# Power.net
KiCad netlist of a schematic drawn in Altium Designer
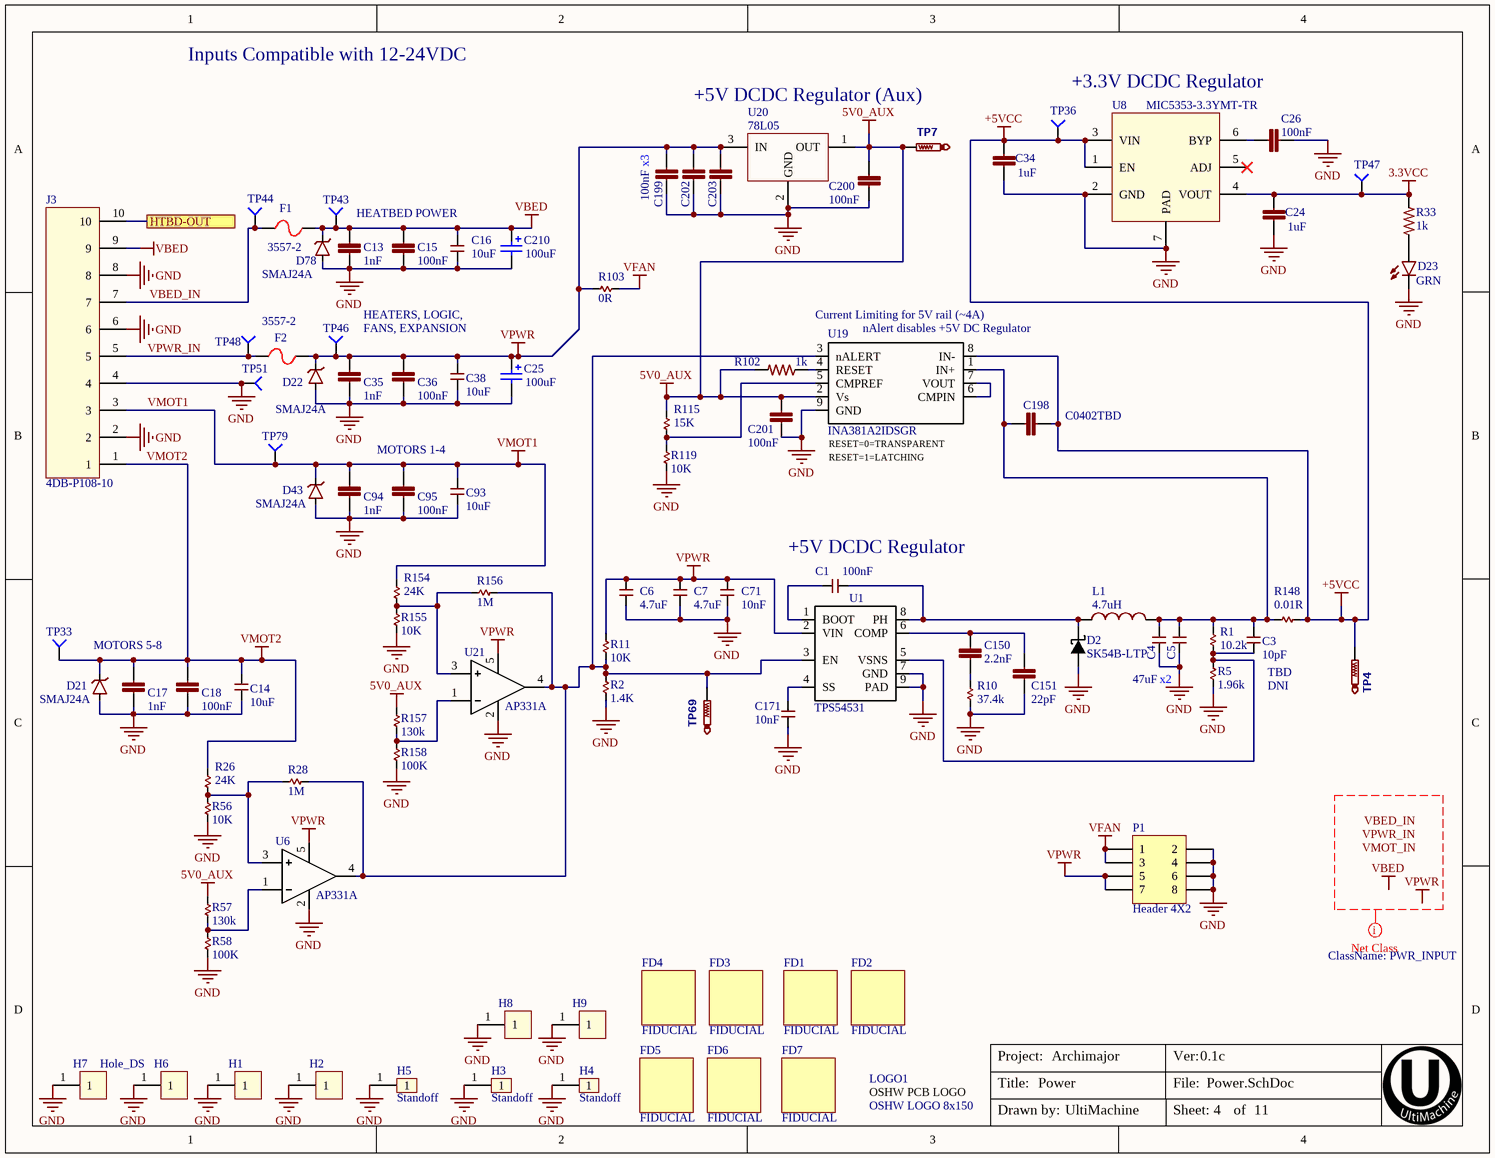
[diagram p0: Power.SchDoc]

(export (version "E")
  (design (tool "Eeschema 10.0.6"))
  (components
    (comp (ref "C1")
      (value "100nF")
      (footprint "C0603")
      (description "CAP CER 0603 100nF 50V 10% X7R")
      (fields (field (name "MANUFACTURER") "Kemet") (field (name "PART") "C0603C104K5RACTU"))
      (libsource (lib "Capacitors") (part "100nF 0603 50V X7R"))
    )
    (comp (ref "C3")
      (value "10pF")
      (footprint "C0402")
      (description "CAP CER 0402 TBD")
      (fields
        (field (name "PART DESCRIPTION") "TBD")
        (field (name "MANUFACTURER") "TBD")
        (field (name "DNI") "DNI")
      )
      (libsource (lib "Capacitors") (part "C0402_TBD"))
    )
    (comp (ref "C4")
      (value "47uF")
      (footprint "C1210")
      (description "CAP CER 47UF 10V X5R 1210")
      (fields (field (name "MANUFACTURER") "Murata") (field (name "PART") "GRM32ER61A476KE20L"))
      (libsource (lib "Capacitors") (part "47uF 1210 10V X5R"))
    )
    (comp (ref "C5")
      (value "47uF")
      (footprint "C1210")
      (description "CAP CER 47UF 10V X5R 1210")
      (fields (field (name "MANUFACTURER") "Murata") (field (name "PART") "GRM32ER61A476KE20L"))
      (libsource (lib "Capacitors") (part "47uF 1210 10V X5R"))
    )
    (comp (ref "C6")
      (value "4.7uF")
      (footprint "C1210")
      (description "CAP CER 4.7UF 50V X7R 1210")
      (fields (field (name "MANUFACTURER") "Murata") (field (name "PART") "GRM32ER71H475KA88L"))
      (libsource (lib "Capacitors") (part "4.7uF 1210 50V X7R"))
    )
    (comp (ref "C7")
      (value "4.7uF")
      (footprint "C1210")
      (description "CAP CER 4.7UF 50V X7R 1210")
      (fields (field (name "MANUFACTURER") "Murata") (field (name "PART") "GRM32ER71H475KA88L"))
      (libsource (lib "Capacitors") (part "4.7uF 1210 50V X7R"))
    )
    (comp (ref "C13")
      (value "1nF")
      (footprint "C0402")
      (description "1000pF 50V Ceramic Capacitor X7R 0402 (1005 Metric) 0.039\" L x 0.020\" W (1.00mm x 0.50mm)")
      (fields (field (name "MANUFACTURER") "Murata") (field (name "PART") "GRM155R71H102KA01D"))
      (libsource (lib "3Delight") (part "CAP 1nF 50V 0402 X7R"))
    )
    (comp (ref "C14")
      (value "10uF")
      (footprint "C1206")
      (description "CAP CER 10UF 50V 10% X5R 1206")
      (fields (field (name "MANUFACTURER") "Murata") (field (name "PART") "490-10756-2-ND"))
      (libsource (lib "Capacitors") (part "10uF 1206 50V X5R"))
    )
    (comp (ref "C15")
      (value "100nF")
      (footprint "C0603")
      (description "CAP CER 0603 100nF 50V 10% X7R")
      (fields (field (name "MANUFACTURER") "Kemet") (field (name "PART") "C0603C104K5RACTU"))
      (libsource (lib "3Delight") (part "C0603C104K5RACTU"))
    )
    (comp (ref "C16")
      (value "10uF")
      (footprint "C1206")
      (description "CAP CER 10UF 50V 10% X5R 1206")
      (fields (field (name "MANUFACTURER") "Murata") (field (name "PART") "490-10756-2-ND"))
      (libsource (lib "Capacitors") (part "10uF 1206 50V X5R"))
    )
    (comp (ref "C17")
      (value "1nF")
      (footprint "C0402")
      (description "1000pF 50V Ceramic Capacitor X7R 0402 (1005 Metric) 0.039\" L x 0.020\" W (1.00mm x 0.50mm)")
      (fields (field (name "MANUFACTURER") "Murata") (field (name "PART") "GRM155R71H102KA01D"))
      (libsource (lib "3Delight") (part "CAP 1nF 50V 0402 X7R"))
    )
    (comp (ref "C18")
      (value "100nF")
      (footprint "C0603")
      (description "CAP CER 0603 100nF 50V 10% X7R")
      (fields (field (name "MANUFACTURER") "Kemet") (field (name "PART") "C0603C104K5RACTU"))
      (libsource (lib "3Delight") (part "C0603C104K5RACTU"))
    )
    (comp (ref "C24")
      (value "1uF")
      (footprint "C0402")
      (description "CAP CER 0402 1uF 6.3V 10% X5R")
      (fields (field (name "MANUFACTURER") "Murata") (field (name "PART") "GRM155R60J105KE19D"))
      (libsource (lib "3Delight") (part "GRM155R60J105KE19D"))
    )
    (comp (ref "C25")
      (value "100uF")
      (footprint "CAP-ELEC-063063077")
      (description "CAP ALUM 100UF 35V 20% SMD")
      (fields (field (name "MANUFACTURER") "Nichicon") (field (name "PART") "UWT1V101MCL1GS"))
      (libsource (lib "3Delight") (part "UWT1V101MCL1GS"))
    )
    (comp (ref "C26")
      (value "100nF")
      (footprint "C0402")
      (description "CAP CER 0402 100nF 16V 10% X7R")
      (fields (field (name "MANUFACTURER") "Murata") (field (name "PART") "GRM155R71C104KA88D"))
      (libsource (lib "") (part "GRM155R71C104KA88D_1"))
    )
    (comp (ref "C34")
      (value "1uF")
      (footprint "C0402")
      (description "CAP CER 0402 1uF 6.3V 10% X5R")
      (fields (field (name "MANUFACTURER") "Murata") (field (name "PART") "GRM155R60J105KE19D"))
      (libsource (lib "3Delight") (part "GRM155R60J105KE19D"))
    )
    (comp (ref "C35")
      (value "1nF")
      (footprint "C0402")
      (description "1000pF 50V Ceramic Capacitor X7R 0402 (1005 Metric) 0.039\" L x 0.020\" W (1.00mm x 0.50mm)")
      (fields (field (name "MANUFACTURER") "Murata") (field (name "PART") "GRM155R71H102KA01D"))
      (libsource (lib "3Delight") (part "CAP 1nF 50V 0402 X7R"))
    )
    (comp (ref "C36")
      (value "100nF")
      (footprint "C0603")
      (description "CAP CER 0603 100nF 50V 10% X7R")
      (fields (field (name "MANUFACTURER") "Kemet") (field (name "PART") "C0603C104K5RACTU"))
      (libsource (lib "3Delight") (part "C0603C104K5RACTU"))
    )
    (comp (ref "C38")
      (value "10uF")
      (footprint "C1206")
      (description "CAP CER 10UF 50V 10% X5R 1206")
      (fields (field (name "MANUFACTURER") "Murata") (field (name "PART") "490-10756-2-ND"))
      (libsource (lib "Capacitors") (part "10uF 1206 50V X5R"))
    )
    (comp (ref "C71")
      (value "10nF")
      (footprint "C0402")
      (description "CAP CER 10nF 50V X7R 0402")
      (fields (field (name "TOLERANCE") "5%") (field (name "MANUFACTURER") "Murata"))
      (libsource (lib "Capacitors") (part "10nF 0402 50V X7R"))
    )
    (comp (ref "C93")
      (value "10uF")
      (footprint "C1206")
      (description "CAP CER 10UF 50V 10% X5R 1206")
      (fields (field (name "MANUFACTURER") "Murata") (field (name "PART") "490-10756-2-ND"))
      (libsource (lib "Capacitors") (part "10uF 1206 50V X5R"))
    )
    (comp (ref "C94")
      (value "1nF")
      (footprint "C0402")
      (description "1000pF 50V Ceramic Capacitor X7R 0402 (1005 Metric) 0.039\" L x 0.020\" W (1.00mm x 0.50mm)")
      (fields (field (name "MANUFACTURER") "Murata") (field (name "PART") "GRM155R71H102KA01D"))
      (libsource (lib "3Delight") (part "CAP 1nF 50V 0402 X7R"))
    )
    (comp (ref "C95")
      (value "100nF")
      (footprint "C0603")
      (description "CAP CER 0603 100nF 50V 10% X7R")
      (fields (field (name "MANUFACTURER") "Kemet") (field (name "PART") "C0603C104K5RACTU"))
      (libsource (lib "3Delight") (part "C0603C104K5RACTU"))
    )
    (comp (ref "C150")
      (value "2.2nF")
      (footprint "C0402")
      (description "CAP CER 0402 2.2nF 25V C0G")
      (fields (field (name "MANUFACTURER") "Kemet") (field (name "PART") "C0402C222J3GACTU"))
      (libsource (lib "Capacitors") (part "2.2nF 25V C0G 0402"))
    )
    (comp (ref "C151")
      (value "22pF")
      (footprint "C0402")
      (description "CAP CER 0402 22pF 50V 5% C0G")
      (fields (field (name "MANUFACTURER") "AVX") (field (name "PART") "04025A220JAT2A"))
      (libsource (lib "Capacitors") (part "22pF 0402 50V C0G"))
    )
    (comp (ref "C171")
      (value "10nF")
      (footprint "C0402")
      (description "CAP CER 10nF 50V X7R 0402")
      (fields (field (name "TOLERANCE") "5%") (field (name "MANUFACTURER") "Murata"))
      (libsource (lib "Capacitors") (part "10nF 0402 50V X7R"))
    )
    (comp (ref "C198")
      (value "C0402TBD")
      (footprint "C0402")
      (description "Capacitor Non Polarized")
      (fields (field (name "PART") "DNI-C0402TBD"))
      (libsource (lib "Capacitors") (part "C0402TBD"))
    )
    (comp (ref "C199")
      (value "100nF")
      (footprint "C0603")
      (description "CAP CER 0603 100nF 50V 10% X7R")
      (fields (field (name "MANUFACTURER") "Kemet") (field (name "PART") "C0603C104K5RACTU"))
      (libsource (lib "3Delight") (part "C0603C104K5RACTU"))
    )
    (comp (ref "C200")
      (value "100nF")
      (footprint "C0402")
      (description "CAP CER 0402 100nF 16V 10% X7R")
      (fields (field (name "MANUFACTURER") "Murata") (field (name "PART") "GRM155R71C104KA88D"))
      (libsource (lib "3Delight") (part "GRM155R71C104KA88D"))
    )
    (comp (ref "C201")
      (value "100nF")
      (footprint "C0402")
      (description "CAP CER 0402 100nF 16V 10% X7R")
      (fields (field (name "MANUFACTURER") "Murata") (field (name "PART") "GRM155R71C104KA88D"))
      (libsource (lib "3Delight") (part "GRM155R71C104KA88D"))
    )
    (comp (ref "C202")
      (value "100nF")
      (footprint "C0603")
      (description "CAP CER 0603 100nF 50V 10% X7R")
      (fields (field (name "MANUFACTURER") "Kemet") (field (name "PART") "C0603C104K5RACTU"))
      (libsource (lib "3Delight") (part "C0603C104K5RACTU"))
    )
    (comp (ref "C203")
      (value "100nF")
      (footprint "C0603")
      (description "CAP CER 0603 100nF 50V 10% X7R")
      (fields (field (name "MANUFACTURER") "Kemet") (field (name "PART") "C0603C104K5RACTU"))
      (libsource (lib "3Delight") (part "C0603C104K5RACTU"))
    )
    (comp (ref "C210")
      (value "100uF")
      (footprint "CAP-ELEC-063063077")
      (description "CAP ALUM 100UF 35V 20% SMD")
      (fields (field (name "MANUFACTURER") "Nichicon") (field (name "PART") "UWT1V101MCL1GS"))
      (libsource (lib "3Delight") (part "UWT1V101MCL1GS"))
    )
    (comp (ref "D2")
      (value "SK54B-LTP")
      (footprint "SMB_DO-214AA_LRG")
      (description "DIODE SCHOTTKY 40V 5A SMB_DO214AA")
      (fields (field (name "MANUFACTURER") "MCC") (field (name "VOLTAGE") "40Vrb"))
      (libsource (lib "Diodes") (part "SK54B"))
    )
    (comp (ref "D21")
      (value "SMAJ24A")
      (footprint "SMA-SM")
      (description "TVS DIODE 24V 38.9V SMA")
      (fields (field (name "MANUFACTURER") "Bourns Inc"))
      (libsource (lib "Diodes") (part "SMAJ24A"))
    )
    (comp (ref "D22")
      (value "SMAJ24A")
      (footprint "SMA-SM")
      (description "TVS DIODE 24V 38.9V SMA")
      (fields (field (name "MANUFACTURER") "Bourns Inc"))
      (libsource (lib "Diodes") (part "SMAJ24A"))
    )
    (comp (ref "D23")
      (value "GRN")
      (footprint "LED2012120")
      (description "LED 0805 Green")
      (fields (field (name "MANUFACTURER") "Dialight") (field (name "PART") "5988170107F"))
      (libsource (lib "LEDs") (part "5988170107F"))
    )
    (comp (ref "D43")
      (value "SMAJ24A")
      (footprint "SMA-SM")
      (description "TVS DIODE 24V 38.9V SMA")
      (fields (field (name "MANUFACTURER") "Bourns Inc"))
      (libsource (lib "Diodes") (part "SMAJ24A"))
    )
    (comp (ref "D78")
      (value "SMAJ24A")
      (footprint "SMA-SM")
      (description "TVS DIODE 24V 38.9V SMA")
      (fields (field (name "MANUFACTURER") "Bourns Inc"))
      (libsource (lib "Diodes") (part "SMAJ24A"))
    )
    (comp (ref "F1")
      (value "3557-2")
      (footprint "3557")
      (description "FUSE PTH ATO")
      (fields (field (name "MANUFACTURER") "Keystone") (field (name "TOLERANCE") "-NA-"))
      (libsource (lib "3Delight") (part "3557-2"))
    )
    (comp (ref "F2")
      (value "3557-2")
      (footprint "3557")
      (description "FUSE PTH ATO")
      (fields (field (name "MANUFACTURER") "Keystone") (field (name "TOLERANCE") "-NA-"))
      (libsource (lib "3Delight") (part "3557-2"))
    )
    (comp (ref "FD1")
      (value "FIDUCIAL")
      (footprint "FIDUCIAL-1X2")
      (fields (field (name "PART") "NOTAPART-Fiducial"))
      (libsource (lib "3Delight") (part "FIDUCIAL"))
    )
    (comp (ref "FD2")
      (value "FIDUCIAL")
      (footprint "FIDUCIAL-1X2")
      (fields (field (name "PART") "NOTAPART-Fiducial"))
      (libsource (lib "3Delight") (part "FIDUCIAL"))
    )
    (comp (ref "FD3")
      (value "FIDUCIAL")
      (footprint "FIDUCIAL-1X2")
      (fields (field (name "PART") "NOTAPART-Fiducial"))
      (libsource (lib "3Delight") (part "FIDUCIAL"))
    )
    (comp (ref "FD4")
      (value "FIDUCIAL")
      (footprint "FIDUCIAL-1X2")
      (fields (field (name "PART") "NOTAPART-Fiducial"))
      (libsource (lib "3Delight") (part "FIDUCIAL"))
    )
    (comp (ref "FD5")
      (value "FIDUCIAL")
      (footprint "FIDUCIAL-1X2")
      (fields (field (name "PART") "NOTAPART-Fiducial"))
      (libsource (lib "3Delight") (part "FIDUCIAL"))
    )
    (comp (ref "FD6")
      (value "FIDUCIAL")
      (footprint "FIDUCIAL-1X2")
      (fields (field (name "PART") "NOTAPART-Fiducial"))
      (libsource (lib "3Delight") (part "FIDUCIAL"))
    )
    (comp (ref "FD7")
      (value "FIDUCIAL")
      (footprint "FIDUCIAL-1X2")
      (fields (field (name "PART") "NOTAPART-Fiducial"))
      (libsource (lib "3Delight") (part "FIDUCIAL"))
    )
    (comp (ref "H1")
      (value "Hole_DS")
      (footprint "Wave_hole_3x7-doubleSided")
      (fields (field (name "PART") "NOTAPART-Hole"))
      (libsource (lib "Archim_0.4") (part "Hole_DS"))
    )
    (comp (ref "H2")
      (value "Hole_DS")
      (footprint "Wave_hole_3x7-doubleSided")
      (fields (field (name "PART") "NOTAPART-Hole"))
      (libsource (lib "Archim_0.4") (part "Hole_DS"))
    )
    (comp (ref "H3")
      (value "Standoff")
      (footprint "Standoff3mmTopConn")
      (description "Mechanical - Top connect")
      (fields (field (name "PART") "NOTAPART-Hole"))
      (libsource (lib "3Delight") (part "Standoff3TopConn"))
    )
    (comp (ref "H4")
      (value "Standoff")
      (footprint "Standoff3mmTopConn")
      (description "Mechanical - Top connect")
      (fields (field (name "PART") "NOTAPART-Hole"))
      (libsource (lib "3Delight") (part "Standoff3TopConn"))
    )
    (comp (ref "H5")
      (value "Standoff")
      (footprint "Standoff3mmTopConn")
      (description "Mechanical - Top connect")
      (fields (field (name "PART") "NOTAPART-Hole"))
      (libsource (lib "3Delight") (part "Standoff3TopConn"))
    )
    (comp (ref "H6")
      (value "Hole_DS")
      (footprint "Wave_hole_3x7-doubleSided")
      (fields (field (name "PART") "NOTAPART-Hole"))
      (libsource (lib "Archim_0.4") (part "Hole_DS"))
    )
    (comp (ref "H7")
      (value "Hole_DS")
      (footprint "Wave_hole_3x7-doubleSided")
      (fields (field (name "PART") "NOTAPART-Hole"))
      (libsource (lib "Archim_0.4") (part "Hole_DS"))
    )
    (comp (ref "H8")
      (value "Hole_DS")
      (footprint "Wave_hole_3x7-doubleSided")
      (fields (field (name "PART") "NOTAPART-Hole"))
      (libsource (lib "Archim_0.4") (part "Hole_DS"))
    )
    (comp (ref "H9")
      (value "Hole_DS")
      (footprint "Wave_hole_3x7-doubleSided")
      (fields (field (name "PART") "NOTAPART-Hole"))
      (libsource (lib "Archim_0.4") (part "Hole_DS"))
    )
    (comp (ref "J3")
      (value "4DB-P108-10")
      (footprint "CON-Barrier-10-8.26mm")
      (description "CONN BARRIER STRIP 10CIRC 0.325\"")
      (fields (field (name "MANUFACTURER") "TE") (field (name "TOLERANCE") "NA"))
      (libsource (lib "Connectors") (part "10 Pos barrier"))
    )
    (comp (ref "L1")
      (value "4.7uH")
      (footprint "IND_10X10")
      (description "FIXED IND 4.7UH 10A 15.5 MOHM")
      (fields (field (name "MANUFACTURER") "Bourns") (field (name "PART") "SRP1038A-4R7M"))
      (libsource (lib "Inductors") (part "4.7uH 10A"))
    )
    (comp (ref "LOGO1")
      (value "OSHW LOGO 8x150")
      (footprint "OSHW_8X150_NOTEXT")
      (fields (field (name "PART") "NOTAPART-OSHW LOGO"))
      (libsource (lib "MISC") (part "OSHW LOGO 8x150"))
    )
    (comp (ref "P1")
      (value "Header 4X2")
      (footprint "HDR2X4")
      (description "Header, 4-Pin, Dual row")
      (fields (field (name "MANUFACTURER") "Multicomp") (field (name "PART") "2213S-08G"))
      (libsource (lib "Miscellaneous Connectors") (part "Header 4X2"))
    )
    (comp (ref "R1")
      (value "10.2k")
      (footprint "R0402")
      (description "RES SMD 10.2K OHM 1% 1/16W 0402")
      (fields (field (name "MANUFACTURER") "Yageo") (field (name "PART") "RC0402FR-0710K2L"))
      (libsource (lib "Resistors") (part "10.2k 1% 0402"))
    )
    (comp (ref "R2")
      (value "1.4K")
      (footprint "R0402")
      (description "RES SMD 1.4K OHM 1% 1/16W 0402")
      (fields (field (name "MANUFACTURER") "Stackpole") (field (name "TOLERANCE") "+/- 1%"))
      (libsource (lib "Resistors") (part "1.4k 1% 0402"))
    )
    (comp (ref "R5")
      (value "1.96k")
      (footprint "R0402")
      (description "RES SMD 1.96K OHM 1% 1/16W 0402")
      (fields (field (name "MANUFACTURER") "Yageo") (field (name "PART") "RC0402FR-071K96L"))
      (libsource (lib "Resistors") (part "1.96k 1% 0402"))
    )
    (comp (ref "R10")
      (value "37.4k")
      (footprint "R0402")
      (description "RES SMD 37.4K OHM 1% 1/16W 0402")
      (fields (field (name "MANUFACTURER") "Yageo") (field (name "PART") "RC0402FR-0737K4L"))
      (libsource (lib "Resistors") (part "37.4K 1% 0402"))
    )
    (comp (ref "R11")
      (value "10K")
      (footprint "R0402")
      (description "RES SMD 10K OHM 1% 1/16W 0402")
      (fields (field (name "MANUFACTURER") "Yageo") (field (name "PART") "RC0402FR-0710KP"))
      (libsource (lib "Resistors") (part "10k 1% 0402"))
    )
    (comp (ref "R26")
      (value "24K")
      (footprint "R0402")
      (description "RES SMD 24K OHM 1% 1/16W 0402")
      (fields (field (name "MANUFACTURER") "Visha Dale") (field (name "TOLERANCE") "+/- 1%"))
      (libsource (lib "Resistors") (part "24k 1% 0402"))
    )
    (comp (ref "R28")
      (value "1M")
      (footprint "Passives:R0402")
      (description "RES 0402 1M 100mW 5%")
      (fields (field (name "MANUFACTURER") "Panasonic") (field (name "PART") "ERJ2GEJ105X"))
      (libsource (lib "Resistors") (part "1M 5% 0402"))
    )
    (comp (ref "R33")
      (value "1k")
      (footprint "R0402")
      (description "RES 0402 1k 63mW 1%")
      (fields (field (name "MANUFACTURER") "Yageo") (field (name "PART") "RC0402FR-071KL"))
      (libsource (lib "3Delight") (part "RK73H1ETTP1001F"))
    )
    (comp (ref "R56")
      (value "10K")
      (footprint "R0402")
      (description "RES SMD 10K OHM 1% 1/16W 0402")
      (fields (field (name "MANUFACTURER") "Yageo") (field (name "PART") "RC0402FR-0710KP"))
      (libsource (lib "Resistors") (part "10k 1% 0402"))
    )
    (comp (ref "R57")
      (value "130k")
      (footprint "Passives:R0402")
      (description "RES SMD 130K OHM 5% 1/16W 0402")
      (fields (field (name "MANUFACTURER") "Yageo") (field (name "PART") "RC0402JR-07130KL"))
      (libsource (lib "Resistors") (part "130k 1% 0402"))
    )
    (comp (ref "R58")
      (value "100K")
      (footprint "Passives:R0402")
      (description "RES SMD 100K OHM 1% 1/16W 0402")
      (fields (field (name "MANUFACTURER") "Samsung") (field (name "PART") "RC1005F104CS"))
      (libsource (lib "Resistors") (part "100k 1% 0402"))
    )
    (comp (ref "R102")
      (value "1k")
      (footprint "R0402")
      (description "RES 0402 1k 63mW 1%")
      (fields (field (name "MANUFACTURER") "Yageo") (field (name "PART") "RC0402FR-071KL"))
      (libsource (lib "3Delight") (part "RK73H1ETTP1001F"))
    )
    (comp (ref "R103")
      (value "0R")
      (footprint "R0603")
      (description "RES SMD 0.0OHM JUMPER 1/10W 0603")
      (fields (field (name "MANUFACTURER") "Bourns") (field (name "PART") "CR0603-J/-000ELF"))
      (libsource (lib "Resistors") (part "0R 0603"))
    )
    (comp (ref "R115")
      (value "15K")
      (footprint "R0402")
      (description "RES SMD 15K 1% 1/16W 0402")
      (fields (field (name "MANUFACTURER") "Samsung") (field (name "PART") "RC1005F153CS"))
      (libsource (lib "Resistors") (part "15K 1% 0402"))
    )
    (comp (ref "R119")
      (value "10K")
      (footprint "R0402")
      (description "RES SMD 10K OHM 1% 1/16W 0402")
      (fields (field (name "MANUFACTURER") "Yageo") (field (name "PART") "RC0402FR-0710KP"))
      (libsource (lib "Resistors") (part "10k 1% 0402"))
    )
    (comp (ref "R148")
      (value "0.01R")
      (footprint "R0805")
      (description "RES 0.01 OHM 1% 1/2W 0805")
      (fields (field (name "MANUFACTURER") "Susumu") (field (name "PART") "KRL1220E-M-R010-F-T5"))
      (libsource (lib "Resistors") (part "0.01R 1% 0805"))
    )
    (comp (ref "R154")
      (value "24K")
      (footprint "R0402")
      (description "RES SMD 24K OHM 1% 1/16W 0402")
      (fields (field (name "MANUFACTURER") "Visha Dale") (field (name "TOLERANCE") "+/- 1%"))
      (libsource (lib "Resistors") (part "24k 1% 0402"))
    )
    (comp (ref "R155")
      (value "10K")
      (footprint "R0402")
      (description "RES SMD 10K OHM 1% 1/16W 0402")
      (fields (field (name "MANUFACTURER") "Yageo") (field (name "PART") "RC0402FR-0710KP"))
      (libsource (lib "Resistors") (part "10k 1% 0402"))
    )
    (comp (ref "R156")
      (value "1M")
      (footprint "Passives:R0402")
      (description "RES 0402 1M 100mW 5%")
      (fields (field (name "MANUFACTURER") "Panasonic") (field (name "PART") "ERJ2GEJ105X"))
      (libsource (lib "Resistors") (part "1M 5% 0402"))
    )
    (comp (ref "R157")
      (value "130k")
      (footprint "Passives:R0402")
      (description "RES SMD 130K OHM 5% 1/16W 0402")
      (fields (field (name "MANUFACTURER") "Yageo") (field (name "PART") "RC0402JR-07130KL"))
      (libsource (lib "Resistors") (part "130k 1% 0402"))
    )
    (comp (ref "R158")
      (value "100K")
      (footprint "Passives:R0402")
      (description "RES SMD 100K OHM 1% 1/16W 0402")
      (fields (field (name "MANUFACTURER") "Samsung") (field (name "PART") "RC1005F104CS"))
      (libsource (lib "Resistors") (part "100k 1% 0402"))
    )
    (comp (ref "TP4")
      (value "TestPoint")
      (footprint "TP1-27")
      (description "Test Point")
      (libsource (lib "") (part "TestPoint_1"))
    )
    (comp (ref "TP7")
      (value "TestPoint")
      (footprint "TP1-27")
      (description "Test Point")
      (libsource (lib "3Delight") (part "TestPoint"))
    )
    (comp (ref "TP33")
      (value "TP4")
      (footprint "TP-2")
      (description "Socket")
      (fields (field (name "PART") "NOTAPART-Testpoint"))
      (libsource (lib "Archim") (part "Socket"))
    )
    (comp (ref "TP36")
      (value "TP4")
      (footprint "TP-2")
      (description "Socket")
      (fields (field (name "PART") "NOTAPART-Testpoint"))
      (libsource (lib "Archim") (part "Socket"))
    )
    (comp (ref "TP43")
      (value "TP4")
      (footprint "TP-2")
      (description "Socket")
      (fields (field (name "PART") "NOTAPART-Testpoint"))
      (libsource (lib "Archim") (part "Socket"))
    )
    (comp (ref "TP44")
      (value "TP4")
      (footprint "TP-2")
      (description "Socket")
      (fields (field (name "PART") "NOTAPART-Testpoint"))
      (libsource (lib "Archim") (part "Socket"))
    )
    (comp (ref "TP46")
      (value "TP4")
      (footprint "TP-2")
      (description "Socket")
      (fields (field (name "PART") "NOTAPART-Testpoint"))
      (libsource (lib "Archim") (part "Socket"))
    )
    (comp (ref "TP47")
      (value "TP4")
      (footprint "TP-2")
      (description "Socket")
      (fields (field (name "PART") "NOTAPART-Testpoint"))
      (libsource (lib "Archim") (part "Socket"))
    )
    (comp (ref "TP48")
      (value "TP4")
      (footprint "TP-2")
      (description "Socket")
      (fields (field (name "PART") "NOTAPART-Testpoint"))
      (libsource (lib "Archim") (part "Socket"))
    )
    (comp (ref "TP51")
      (value "TP4")
      (footprint "TP-2")
      (description "Socket")
      (fields (field (name "PART") "NOTAPART-Testpoint"))
      (libsource (lib "Archim") (part "Socket"))
    )
    (comp (ref "TP69")
      (value "TestPoint")
      (footprint "TP1-27")
      (description "Test Point")
      (libsource (lib "") (part "TestPoint_1"))
    )
    (comp (ref "TP79")
      (value "TP4")
      (footprint "TP-2")
      (description "Socket")
      (fields (field (name "PART") "NOTAPART-Testpoint"))
      (libsource (lib "Archim") (part "Socket"))
    )
    (comp (ref "U1")
      (value "TPS54531")
      (footprint "SOIC127P600X170_HS-9L")
      (description "IC REG BUCK ADJ 5A 8SOPWRPAD")
      (fields (field (name "MANUFACTURER") "TI") (field (name "PART") "TPS54531DDAR"))
      (libsource (lib "ICs-Power") (part "TPS54531"))
    )
    (comp (ref "U6")
      (value "AP331A")
      (footprint "SOT23-5")
      (description "IC QUAD DIFF COMPARATOR 14 -SOIC")
      (fields (field (name "PART") "AP331AWG-7") (field (name "MANUFACTURER") "TEXAS INSTRUMENTS"))
      (libsource (lib "ICs-Analog") (part "AP331A"))
    )
    (comp (ref "U8")
      (value "MIC5353-3.3YMT-TR")
      (footprint "TDFN1616-6LD-PL-1")
      (description "LDO 3.3V 500mA - low ESR Cout")
      (fields (field (name "MANUFACTURER") "Microchip") (field (name "TOLERANCE") "-NA-"))
      (libsource (lib "Tigershark3D") (part "MIC5353-3.3YMT-TR"))
    )
    (comp (ref "U19")
      (value "INA381A2IDSGR")
      (footprint "WSON8_2x2mm")
      (description "IC COMPARATOR BIDIR 8WSON")
      (fields (field (name "MANUFACTURER") "TI") (field (name "TOLERANCE") "-NA-"))
      (libsource (lib "ICs-Analog") (part "INA381_ALT"))
    )
    (comp (ref "U20")
      (value "78L05")
      (footprint "SOT-89-3")
      (description "IC REG LINEAR 5V 100MA SOT89-3")
      (fields (field (name "MANUFACTURER") "ST") (field (name "PART") "L78L05ABUTR"))
      (libsource (lib "ICs-Power") (part "78L05"))
    )
    (comp (ref "U21")
      (value "AP331A")
      (footprint "SOT23-5")
      (description "IC QUAD DIFF COMPARATOR 14 -SOIC")
      (fields (field (name "PART") "AP331AWG-7") (field (name "MANUFACTURER") "TEXAS INSTRUMENTS"))
      (libsource (lib "ICs-Analog") (part "AP331A"))
    )
  )
  (nets
    (net (code "1") (name "+5VCC") (class "Default")
      (node (ref "C198") (pin "1") (pinfunction "1_1") (pintype "passive"))
      (node (ref "C34") (pin "1") (pinfunction "1_1") (pintype "passive"))
      (node (ref "R148") (pin "2") (pinfunction "2_2") (pintype "passive"))
      (node (ref "TP36") (pin "1") (pinfunction "1_1") (pintype "passive"))
      (node (ref "TP4") (pin "TP") (pinfunction "TP_TP") (pintype "passive"))
      (node (ref "U19") (pin "8") (pinfunction "IN-_8") (pintype "power_in"))
      (node (ref "U8") (pin "1") (pinfunction "EN_1") (pintype "power_in"))
      (node (ref "U8") (pin "3") (pinfunction "VIN_3") (pintype "power_in"))
    )
    (net (code "2") (name "/HTBD-OUT") (class "Default")
      (node (ref "J3") (pin "10") (pinfunction "10_10") (pintype "passive"))
    )
    (net (code "3") (name "/VBED_IN") (class "Default")
      (node (ref "F1") (pin "1") (pinfunction "1_1") (pintype "passive"))
      (node (ref "J3") (pin "7") (pinfunction "7_7") (pintype "passive"))
      (node (ref "TP44") (pin "1") (pinfunction "1_1") (pintype "passive"))
    )
    (net (code "5") (name "/VPWR_IN") (class "Default")
      (node (ref "F2") (pin "1") (pinfunction "1_1") (pintype "passive"))
      (node (ref "J3") (pin "5") (pinfunction "5_5") (pintype "passive"))
      (node (ref "TP48") (pin "1") (pinfunction "1_1") (pintype "passive"))
    )
    (net (code "6") (name "3.3VCC") (class "Default")
      (node (ref "C24") (pin "1") (pinfunction "1_1") (pintype "passive"))
      (node (ref "R33") (pin "2") (pinfunction "2_2") (pintype "passive"))
      (node (ref "TP47") (pin "1") (pinfunction "1_1") (pintype "passive"))
      (node (ref "U8") (pin "4") (pinfunction "VOUT_4") (pintype "power_in"))
    )
    (net (code "7") (name "5V0_AUX") (class "Default")
      (node (ref "C200") (pin "2") (pinfunction "2_2") (pintype "passive"))
      (node (ref "C201") (pin "2") (pinfunction "2_2") (pintype "passive"))
      (node (ref "R102") (pin "2") (pinfunction "2_2") (pintype "passive"))
      (node (ref "R115") (pin "2") (pinfunction "2_2") (pintype "passive"))
      (node (ref "R157") (pin "2") (pinfunction "2_2") (pintype "passive"))
      (node (ref "R57") (pin "2") (pinfunction "2_2") (pintype "passive"))
      (node (ref "TP7") (pin "TP") (pinfunction "TP_TP") (pintype "passive"))
      (node (ref "U19") (pin "2") (pinfunction "Vs_2") (pintype "power_in"))
      (node (ref "U20") (pin "1") (pinfunction "OUT_1") (pintype "power_in"))
    )
    (net (code "8") (name "GND") (class "Default")
      (node (ref "C13") (pin "2") (pinfunction "2_2") (pintype "passive"))
      (node (ref "C14") (pin "1") (pinfunction "1_1") (pintype "passive"))
      (node (ref "C15") (pin "2") (pinfunction "2_2") (pintype "passive"))
      (node (ref "C151") (pin "1") (pinfunction "1_1") (pintype "passive"))
      (node (ref "C16") (pin "1") (pinfunction "1_1") (pintype "passive"))
      (node (ref "C17") (pin "2") (pinfunction "2_2") (pintype "passive"))
      (node (ref "C171") (pin "1") (pinfunction "1_1") (pintype "passive"))
      (node (ref "C18") (pin "2") (pinfunction "2_2") (pintype "passive"))
      (node (ref "C199") (pin "2") (pinfunction "2_2") (pintype "passive"))
      (node (ref "C200") (pin "1") (pinfunction "1_1") (pintype "passive"))
      (node (ref "C201") (pin "1") (pinfunction "1_1") (pintype "passive"))
      (node (ref "C202") (pin "2") (pinfunction "2_2") (pintype "passive"))
      (node (ref "C203") (pin "2") (pinfunction "2_2") (pintype "passive"))
      (node (ref "C210") (pin "2") (pinfunction "2_2") (pintype "passive"))
      (node (ref "C24") (pin "2") (pinfunction "2_2") (pintype "passive"))
      (node (ref "C25") (pin "2") (pinfunction "2_2") (pintype "passive"))
      (node (ref "C26") (pin "2") (pinfunction "2_2") (pintype "passive"))
      (node (ref "C34") (pin "2") (pinfunction "2_2") (pintype "passive"))
      (node (ref "C35") (pin "2") (pinfunction "2_2") (pintype "passive"))
      (node (ref "C36") (pin "2") (pinfunction "2_2") (pintype "passive"))
      (node (ref "C38") (pin "1") (pinfunction "1_1") (pintype "passive"))
      (node (ref "C4") (pin "1") (pinfunction "1_1") (pintype "passive"))
      (node (ref "C5") (pin "1") (pinfunction "1_1") (pintype "passive"))
      (node (ref "C6") (pin "1") (pinfunction "1_1") (pintype "passive"))
      (node (ref "C7") (pin "1") (pinfunction "1_1") (pintype "passive"))
      (node (ref "C71") (pin "1") (pinfunction "1_1") (pintype "passive"))
      (node (ref "C93") (pin "1") (pinfunction "1_1") (pintype "passive"))
      (node (ref "C94") (pin "2") (pinfunction "2_2") (pintype "passive"))
      (node (ref "C95") (pin "2") (pinfunction "2_2") (pintype "passive"))
      (node (ref "D2") (pin "A") (pinfunction "ANODE_A") (pintype "passive"))
      (node (ref "D21") (pin "A") (pinfunction "A_A") (pintype "passive"))
      (node (ref "D22") (pin "A") (pinfunction "A_A") (pintype "passive"))
      (node (ref "D23") (pin "C") (pinfunction "C_C") (pintype "passive"))
      (node (ref "D43") (pin "A") (pinfunction "A_A") (pintype "passive"))
      (node (ref "D78") (pin "A") (pinfunction "A_A") (pintype "passive"))
      (node (ref "H1") (pin "1") (pinfunction "1_1") (pintype "power_in"))
      (node (ref "H2") (pin "1") (pinfunction "1_1") (pintype "power_in"))
      (node (ref "H3") (pin "1") (pinfunction "1_1") (pintype "power_in"))
      (node (ref "H4") (pin "1") (pinfunction "1_1") (pintype "power_in"))
      (node (ref "H5") (pin "1") (pinfunction "1_1") (pintype "power_in"))
      (node (ref "H6") (pin "1") (pinfunction "1_1") (pintype "power_in"))
      (node (ref "H7") (pin "1") (pinfunction "1_1") (pintype "power_in"))
      (node (ref "H8") (pin "1") (pinfunction "1_1") (pintype "power_in"))
      (node (ref "H9") (pin "1") (pinfunction "1_1") (pintype "power_in"))
      (node (ref "J3") (pin "2") (pinfunction "2_2") (pintype "passive"))
      (node (ref "J3") (pin "4") (pinfunction "4_4") (pintype "passive"))
      (node (ref "J3") (pin "6") (pinfunction "6_6") (pintype "passive"))
      (node (ref "J3") (pin "8") (pinfunction "8_8") (pintype "passive"))
      (node (ref "P1") (pin "2") (pinfunction "2_2") (pintype "passive"))
      (node (ref "P1") (pin "4") (pinfunction "4_4") (pintype "passive"))
      (node (ref "P1") (pin "6") (pinfunction "6_6") (pintype "passive"))
      (node (ref "P1") (pin "8") (pinfunction "8_8") (pintype "passive"))
      (node (ref "R10") (pin "1") (pinfunction "1_1") (pintype "passive"))
      (node (ref "R119") (pin "1") (pinfunction "1_1") (pintype "passive"))
      (node (ref "R155") (pin "1") (pinfunction "1_1") (pintype "passive"))
      (node (ref "R158") (pin "1") (pinfunction "1_1") (pintype "passive"))
      (node (ref "R2") (pin "1") (pinfunction "1_1") (pintype "passive"))
      (node (ref "R5") (pin "1") (pinfunction "1_1") (pintype "passive"))
      (node (ref "R56") (pin "1") (pinfunction "1_1") (pintype "passive"))
      (node (ref "R58") (pin "1") (pinfunction "1_1") (pintype "passive"))
      (node (ref "TP51") (pin "1") (pinfunction "1_1") (pintype "passive"))
      (node (ref "U1") (pin "7") (pinfunction "GND_7") (pintype "passive"))
      (node (ref "U1") (pin "9") (pinfunction "PAD_9") (pintype "passive"))
      (node (ref "U19") (pin "9") (pinfunction "GND_9") (pintype "power_in"))
      (node (ref "U20") (pin "2") (pinfunction "GND_2") (pintype "power_in"))
      (node (ref "U21") (pin "2") (pinfunction "GND_2") (pintype "power_in"))
      (node (ref "U6") (pin "2") (pinfunction "GND_2") (pintype "power_in"))
      (node (ref "U8") (pin "2") (pinfunction "GND_2") (pintype "power_in"))
      (node (ref "U8") (pin "7") (pinfunction "PAD_7") (pintype "power_in"))
    )
    (net (code "9") (name "Net-(C150-Pad1)") (class "Default")
      (node (ref "C150") (pin "1") (pinfunction "1_1") (pintype "passive"))
      (node (ref "R10") (pin "2") (pinfunction "2_2") (pintype "passive"))
    )
    (net (code "10") (name "Net-(D2-CATHODE)") (class "Default")
      (node (ref "C1") (pin "2") (pinfunction "2_2") (pintype "passive"))
      (node (ref "D2") (pin "K") (pinfunction "CATHODE_K") (pintype "passive"))
      (node (ref "L1") (pin "1") (pinfunction "1_1") (pintype "passive"))
      (node (ref "U1") (pin "8") (pinfunction "PH_8") (pintype "passive"))
    )
    (net (code "11") (name "Net-(D23-PadA)") (class "Default")
      (node (ref "D23") (pin "A") (pinfunction "A_A") (pintype "passive"))
      (node (ref "R33") (pin "1") (pinfunction "1_1") (pintype "passive"))
    )
    (net (code "12") (name "Net-(U1-BOOT)") (class "Default")
      (node (ref "C1") (pin "1") (pinfunction "1_1") (pintype "passive"))
      (node (ref "U1") (pin "1") (pinfunction "BOOT_1") (pintype "passive"))
    )
    (net (code "13") (name "Net-(U1-COMP)") (class "Default")
      (node (ref "C150") (pin "2") (pinfunction "2_2") (pintype "passive"))
      (node (ref "C151") (pin "2") (pinfunction "2_2") (pintype "passive"))
      (node (ref "U1") (pin "6") (pinfunction "COMP_6") (pintype "passive"))
    )
    (net (code "14") (name "Net-(U1-EN)") (class "Default")
      (node (ref "R11") (pin "1") (pinfunction "1_1") (pintype "passive"))
      (node (ref "R156") (pin "1") (pinfunction "1_1") (pintype "passive"))
      (node (ref "R2") (pin "2") (pinfunction "2_2") (pintype "passive"))
      (node (ref "R28") (pin "1") (pinfunction "1_1") (pintype "passive"))
      (node (ref "TP69") (pin "TP") (pinfunction "TP_TP") (pintype "passive"))
      (node (ref "U1") (pin "3") (pinfunction "EN_3") (pintype "passive"))
      (node (ref "U19") (pin "3") (pinfunction "nALERT_3") (pintype "power_in"))
      (node (ref "U21") (pin "4") (pinfunction "OUT_4") (pintype "passive"))
      (node (ref "U6") (pin "4") (pinfunction "OUT_4") (pintype "passive"))
    )
    (net (code "15") (name "Net-(U1-SS)") (class "Default")
      (node (ref "C171") (pin "2") (pinfunction "2_2") (pintype "passive"))
      (node (ref "U1") (pin "4") (pinfunction "SS_4") (pintype "passive"))
    )
    (net (code "16") (name "Net-(U1-VSNS)") (class "Default")
      (node (ref "C3") (pin "1") (pinfunction "1_1") (pintype "passive"))
      (node (ref "R1") (pin "2") (pinfunction "2_2") (pintype "passive"))
      (node (ref "R5") (pin "2") (pinfunction "2_2") (pintype "passive"))
      (node (ref "U1") (pin "5") (pinfunction "VSNS_5") (pintype "passive"))
    )
    (net (code "17") (name "Net-(U6-IN+)") (class "Default")
      (node (ref "R26") (pin "2") (pinfunction "2_2") (pintype "passive"))
      (node (ref "R28") (pin "2") (pinfunction "2_2") (pintype "passive"))
      (node (ref "R56") (pin "2") (pinfunction "2_2") (pintype "passive"))
      (node (ref "U6") (pin "3") (pinfunction "IN+_3") (pintype "passive"))
    )
    (net (code "18") (name "Net-(U6-IN-)") (class "Default")
      (node (ref "R57") (pin "1") (pinfunction "1_1") (pintype "passive"))
      (node (ref "R58") (pin "2") (pinfunction "2_2") (pintype "passive"))
      (node (ref "U6") (pin "1") (pinfunction "IN-_1") (pintype "passive"))
    )
    (net (code "19") (name "Net-(U8-BYP)") (class "Default")
      (node (ref "C26") (pin "1") (pinfunction "1_1") (pintype "passive"))
      (node (ref "U8") (pin "6") (pinfunction "BYP_6") (pintype "power_in"))
    )
    (net (code "20") (name "Net-(U19-CMPIN)") (class "Default")
      (node (ref "U19") (pin "6") (pinfunction "CMPIN_6") (pintype "power_in"))
      (node (ref "U19") (pin "7") (pinfunction "VOUT_7") (pintype "power_in"))
    )
    (net (code "21") (name "Net-(U19-CMPREF)") (class "Default")
      (node (ref "R115") (pin "1") (pinfunction "1_1") (pintype "passive"))
      (node (ref "R119") (pin "2") (pinfunction "2_2") (pintype "passive"))
      (node (ref "U19") (pin "5") (pinfunction "CMPREF_5") (pintype "power_in"))
    )
    (net (code "22") (name "Net-(U19-IN+)") (class "Default")
      (node (ref "C198") (pin "2") (pinfunction "2_2") (pintype "passive"))
      (node (ref "C3") (pin "2") (pinfunction "2_2") (pintype "passive"))
      (node (ref "C4") (pin "2") (pinfunction "2_2") (pintype "passive"))
      (node (ref "C5") (pin "2") (pinfunction "2_2") (pintype "passive"))
      (node (ref "L1") (pin "2") (pinfunction "2_2") (pintype "passive"))
      (node (ref "R1") (pin "1") (pinfunction "1_1") (pintype "passive"))
      (node (ref "R148") (pin "1") (pinfunction "1_1") (pintype "passive"))
      (node (ref "U19") (pin "1") (pinfunction "IN+_1") (pintype "power_in"))
    )
    (net (code "23") (name "Net-(U19-RESET)") (class "Default")
      (node (ref "R102") (pin "1") (pinfunction "1_1") (pintype "passive"))
      (node (ref "U19") (pin "4") (pinfunction "RESET_4") (pintype "power_in"))
    )
    (net (code "24") (name "Net-(U21-IN+)") (class "Default")
      (node (ref "R154") (pin "2") (pinfunction "2_2") (pintype "passive"))
      (node (ref "R155") (pin "2") (pinfunction "2_2") (pintype "passive"))
      (node (ref "R156") (pin "2") (pinfunction "2_2") (pintype "passive"))
      (node (ref "U21") (pin "3") (pinfunction "IN+_3") (pintype "passive"))
    )
    (net (code "25") (name "Net-(U21-IN-)") (class "Default")
      (node (ref "R157") (pin "1") (pinfunction "1_1") (pintype "passive"))
      (node (ref "R158") (pin "2") (pinfunction "2_2") (pintype "passive"))
      (node (ref "U21") (pin "1") (pinfunction "IN-_1") (pintype "passive"))
    )
    (net (code "26") (name "VBED") (class "Default")
      (node (ref "C13") (pin "1") (pinfunction "1_1") (pintype "passive"))
      (node (ref "C15") (pin "1") (pinfunction "1_1") (pintype "passive"))
      (node (ref "C16") (pin "2") (pinfunction "2_2") (pintype "passive"))
      (node (ref "C210") (pin "1") (pinfunction "1_1") (pintype "passive"))
      (node (ref "D78") (pin "K") (pinfunction "K_K") (pintype "passive"))
      (node (ref "F1") (pin "2") (pinfunction "2_2") (pintype "passive"))
      (node (ref "J3") (pin "9") (pinfunction "9_9") (pintype "passive"))
      (node (ref "TP43") (pin "1") (pinfunction "1_1") (pintype "passive"))
    )
    (net (code "27") (name "VFAN") (class "Default")
      (node (ref "P1") (pin "1") (pinfunction "1_1") (pintype "passive"))
      (node (ref "P1") (pin "3") (pinfunction "3_3") (pintype "passive"))
      (node (ref "R103") (pin "2") (pinfunction "2_2") (pintype "passive"))
    )
    (net (code "28") (name "VMOT1") (class "Default")
      (node (ref "C93") (pin "2") (pinfunction "2_2") (pintype "passive"))
      (node (ref "C94") (pin "1") (pinfunction "1_1") (pintype "passive"))
      (node (ref "C95") (pin "1") (pinfunction "1_1") (pintype "passive"))
      (node (ref "D43") (pin "K") (pinfunction "K_K") (pintype "passive"))
      (node (ref "J3") (pin "3") (pinfunction "3_3") (pintype "passive"))
      (node (ref "R154") (pin "1") (pinfunction "1_1") (pintype "passive"))
      (node (ref "TP79") (pin "1") (pinfunction "1_1") (pintype "passive"))
    )
    (net (code "29") (name "VMOT2") (class "Default")
      (node (ref "C14") (pin "2") (pinfunction "2_2") (pintype "passive"))
      (node (ref "C17") (pin "1") (pinfunction "1_1") (pintype "passive"))
      (node (ref "C18") (pin "1") (pinfunction "1_1") (pintype "passive"))
      (node (ref "D21") (pin "K") (pinfunction "K_K") (pintype "passive"))
      (node (ref "J3") (pin "1") (pinfunction "1_1") (pintype "passive"))
      (node (ref "R26") (pin "1") (pinfunction "1_1") (pintype "passive"))
      (node (ref "TP33") (pin "1") (pinfunction "1_1") (pintype "passive"))
    )
    (net (code "30") (name "VPWR") (class "Default")
      (node (ref "C199") (pin "1") (pinfunction "1_1") (pintype "passive"))
      (node (ref "C202") (pin "1") (pinfunction "1_1") (pintype "passive"))
      (node (ref "C203") (pin "1") (pinfunction "1_1") (pintype "passive"))
      (node (ref "C25") (pin "1") (pinfunction "1_1") (pintype "passive"))
      (node (ref "C35") (pin "1") (pinfunction "1_1") (pintype "passive"))
      (node (ref "C36") (pin "1") (pinfunction "1_1") (pintype "passive"))
      (node (ref "C38") (pin "2") (pinfunction "2_2") (pintype "passive"))
      (node (ref "C6") (pin "2") (pinfunction "2_2") (pintype "passive"))
      (node (ref "C7") (pin "2") (pinfunction "2_2") (pintype "passive"))
      (node (ref "C71") (pin "2") (pinfunction "2_2") (pintype "passive"))
      (node (ref "D22") (pin "K") (pinfunction "K_K") (pintype "passive"))
      (node (ref "F2") (pin "2") (pinfunction "2_2") (pintype "passive"))
      (node (ref "P1") (pin "5") (pinfunction "5_5") (pintype "passive"))
      (node (ref "P1") (pin "7") (pinfunction "7_7") (pintype "passive"))
      (node (ref "R103") (pin "1") (pinfunction "1_1") (pintype "passive"))
      (node (ref "R11") (pin "2") (pinfunction "2_2") (pintype "passive"))
      (node (ref "TP46") (pin "1") (pinfunction "1_1") (pintype "passive"))
      (node (ref "U1") (pin "2") (pinfunction "VIN_2") (pintype "passive"))
      (node (ref "U20") (pin "3") (pinfunction "IN_3") (pintype "power_in"))
      (node (ref "U21") (pin "5") (pinfunction "VCC_5") (pintype "power_in"))
      (node (ref "U6") (pin "5") (pinfunction "VCC_5") (pintype "power_in"))
    )
    (net (code "31") (name "unconnected-(U8-ADJ-Pad5)") (class "Default")
      (node (ref "U8") (pin "5") (pinfunction "ADJ_5") (pintype "power_in+no_connect"))
    )
  )
)
